# 2_Sensors.net
KiCad netlist of a schematic drawn in Altium Designer
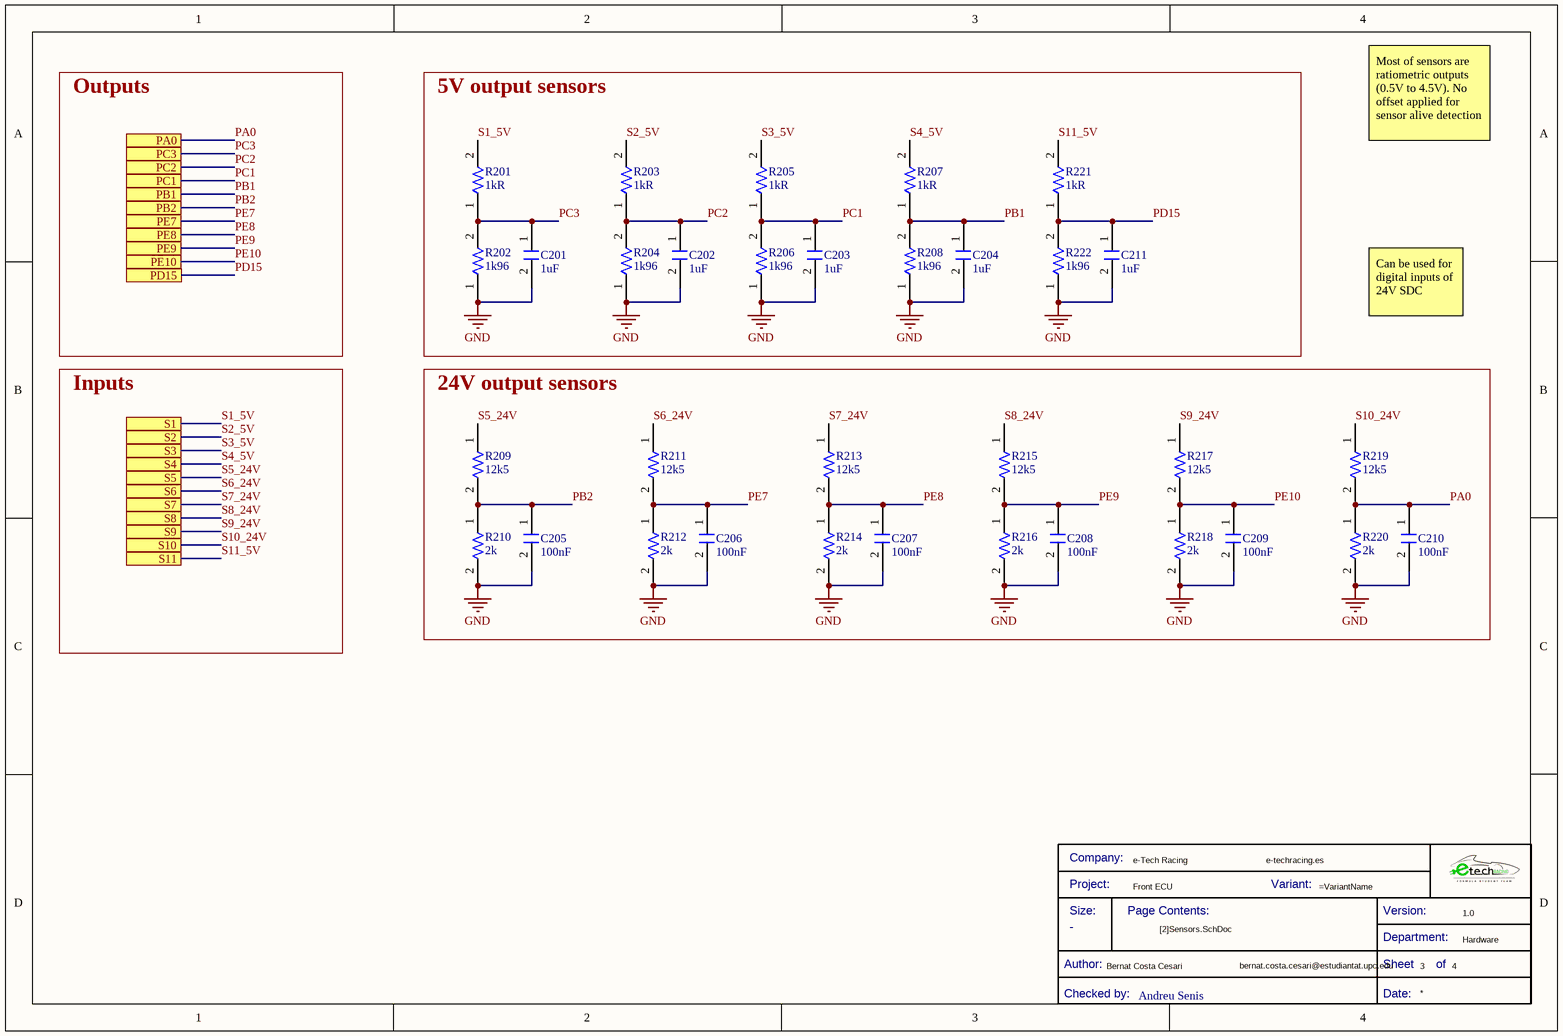
[diagram p0: [2]Sensors.SchDoc]

(export (version "E")
  (design (tool "Eeschema 10.0.6"))
  (components
    (comp (ref "C201")
      (value "885012207103")
      (footprint "C0805FNPC-R")
      (fields
        (field (name "TOLERANCE") "10%")
        (field (name "CAPACITANCE") "1uF")
        (field (name ".CREATOR") "GP")
      )
      (libsource (lib "Passives") (part "C1u-50V-0805FNPC-X7R"))
    )
    (comp (ref "C202")
      (value "885012207103")
      (footprint "C0805FNPC-R")
      (fields
        (field (name "TOLERANCE") "10%")
        (field (name "CAPACITANCE") "1uF")
        (field (name ".CREATOR") "GP")
      )
      (libsource (lib "Passives") (part "C1u-50V-0805FNPC-X7R"))
    )
    (comp (ref "C203")
      (value "885012207103")
      (footprint "C0805FNPC-R")
      (fields
        (field (name "TOLERANCE") "10%")
        (field (name "CAPACITANCE") "1uF")
        (field (name ".CREATOR") "GP")
      )
      (libsource (lib "Passives") (part "C1u-50V-0805FNPC-X7R"))
    )
    (comp (ref "C204")
      (value "885012207103")
      (footprint "C0805FNPC-R")
      (fields
        (field (name "TOLERANCE") "10%")
        (field (name "CAPACITANCE") "1uF")
        (field (name ".CREATOR") "GP")
      )
      (libsource (lib "Passives") (part "C1u-50V-0805FNPC-X7R"))
    )
    (comp (ref "C205")
      (value "885012207098")
      (footprint "C0805FNPC-R")
      (description "Cap, 0.1ΜF, 50V, 10%, X7R, 0805")
      (fields
        (field (name "TOLERANCE") "10%")
        (field (name "CAPACITANCE") "100nF")
        (field (name ".CREATOR") "DR")
      )
      (libsource (lib "Passives") (part "C100n-50V-0805FNPC-X7R"))
    )
    (comp (ref "C206")
      (value "885012207098")
      (footprint "C0805FNPC-R")
      (description "Cap, 0.1ΜF, 50V, 10%, X7R, 0805")
      (fields
        (field (name "TOLERANCE") "10%")
        (field (name "CAPACITANCE") "100nF")
        (field (name ".CREATOR") "DR")
      )
      (libsource (lib "Passives") (part "C100n-50V-0805FNPC-X7R"))
    )
    (comp (ref "C207")
      (value "885012207098")
      (footprint "C0805FNPC-R")
      (description "Cap, 0.1ΜF, 50V, 10%, X7R, 0805")
      (fields
        (field (name "TOLERANCE") "10%")
        (field (name "CAPACITANCE") "100nF")
        (field (name ".CREATOR") "DR")
      )
      (libsource (lib "Passives") (part "C100n-50V-0805FNPC-X7R"))
    )
    (comp (ref "C208")
      (value "885012207098")
      (footprint "C0805FNPC-R")
      (description "Cap, 0.1ΜF, 50V, 10%, X7R, 0805")
      (fields
        (field (name "TOLERANCE") "10%")
        (field (name "CAPACITANCE") "100nF")
        (field (name ".CREATOR") "DR")
      )
      (libsource (lib "Passives") (part "C100n-50V-0805FNPC-X7R"))
    )
    (comp (ref "C209")
      (value "885012207098")
      (footprint "C0805FNPC-R")
      (description "Cap, 0.1ΜF, 50V, 10%, X7R, 0805")
      (fields
        (field (name "TOLERANCE") "10%")
        (field (name "CAPACITANCE") "100nF")
        (field (name ".CREATOR") "DR")
      )
      (libsource (lib "Passives") (part "C100n-50V-0805FNPC-X7R"))
    )
    (comp (ref "C210")
      (value "885012207098")
      (footprint "C0805FNPC-R")
      (description "Cap, 0.1ΜF, 50V, 10%, X7R, 0805")
      (fields
        (field (name "TOLERANCE") "10%")
        (field (name "CAPACITANCE") "100nF")
        (field (name ".CREATOR") "DR")
      )
      (libsource (lib "Passives") (part "C100n-50V-0805FNPC-X7R"))
    )
    (comp (ref "C211")
      (value "885012207103")
      (footprint "C0805FNPC-R")
      (fields
        (field (name "TOLERANCE") "10%")
        (field (name "CAPACITANCE") "1uF")
        (field (name ".CREATOR") "GP")
      )
      (libsource (lib "Passives") (part "C1u-50V-0805FNPC-X7R"))
    )
    (comp (ref "R201")
      (value "CR0805-JW-102ELF")
      (footprint "R0805FTK")
      (description "Res Thick Film 0805 1K Ohm 5% 1/8W ±200ppm/°C Molded SMD SMD Paper Tape on Plastic Reel")
      (fields
        (field (name "TOLERANCE") "5%")
        (field (name "RESISTANCE") "1kR")
        (field (name ".CREATOR") "GP")
      )
      (libsource (lib "Passives") (part "R1k-0805FTK"))
    )
    (comp (ref "R202")
      (value "1k96")
      (footprint "R0805FTK")
      (libsource (lib "Passives") (part "R1k96-0805FTK"))
    )
    (comp (ref "R203")
      (value "CR0805-JW-102ELF")
      (footprint "R0805FTK")
      (description "Res Thick Film 0805 1K Ohm 5% 1/8W ±200ppm/°C Molded SMD SMD Paper Tape on Plastic Reel")
      (fields
        (field (name "TOLERANCE") "5%")
        (field (name "RESISTANCE") "1kR")
        (field (name ".CREATOR") "GP")
      )
      (libsource (lib "Passives") (part "R1k-0805FTK"))
    )
    (comp (ref "R204")
      (value "1k96")
      (footprint "R0805FTK")
      (libsource (lib "Passives") (part "R1k96-0805FTK"))
    )
    (comp (ref "R205")
      (value "CR0805-JW-102ELF")
      (footprint "R0805FTK")
      (description "Res Thick Film 0805 1K Ohm 5% 1/8W ±200ppm/°C Molded SMD SMD Paper Tape on Plastic Reel")
      (fields
        (field (name "TOLERANCE") "5%")
        (field (name "RESISTANCE") "1kR")
        (field (name ".CREATOR") "GP")
      )
      (libsource (lib "Passives") (part "R1k-0805FTK"))
    )
    (comp (ref "R206")
      (value "1k96")
      (footprint "R0805FTK")
      (libsource (lib "Passives") (part "R1k96-0805FTK"))
    )
    (comp (ref "R207")
      (value "CR0805-JW-102ELF")
      (footprint "R0805FTK")
      (description "Res Thick Film 0805 1K Ohm 5% 1/8W ±200ppm/°C Molded SMD SMD Paper Tape on Plastic Reel")
      (fields
        (field (name "TOLERANCE") "5%")
        (field (name "RESISTANCE") "1kR")
        (field (name ".CREATOR") "GP")
      )
      (libsource (lib "Passives") (part "R1k-0805FTK"))
    )
    (comp (ref "R208")
      (value "1k96")
      (footprint "R0805FTK")
      (libsource (lib "Passives") (part "R1k96-0805FTK"))
    )
    (comp (ref "R209")
      (value "12k5")
      (footprint "R0805FTK")
      (libsource (lib "Passives") (part "R12k5-0805FTK"))
    )
    (comp (ref "R210") (value "2k") (footprint "R0805FTK") (libsource (lib "Passives") (part "R2k-0805FTK")))
    (comp (ref "R211")
      (value "12k5")
      (footprint "R0805FTK")
      (libsource (lib "Passives") (part "R12k5-0805FTK"))
    )
    (comp (ref "R212") (value "2k") (footprint "R0805FTK") (libsource (lib "Passives") (part "R2k-0805FTK")))
    (comp (ref "R213")
      (value "12k5")
      (footprint "R0805FTK")
      (libsource (lib "Passives") (part "R12k5-0805FTK"))
    )
    (comp (ref "R214") (value "2k") (footprint "R0805FTK") (libsource (lib "Passives") (part "R2k-0805FTK")))
    (comp (ref "R215")
      (value "12k5")
      (footprint "R0805FTK")
      (libsource (lib "Passives") (part "R12k5-0805FTK"))
    )
    (comp (ref "R216") (value "2k") (footprint "R0805FTK") (libsource (lib "Passives") (part "R2k-0805FTK")))
    (comp (ref "R217")
      (value "12k5")
      (footprint "R0805FTK")
      (libsource (lib "Passives") (part "R12k5-0805FTK"))
    )
    (comp (ref "R218") (value "2k") (footprint "R0805FTK") (libsource (lib "Passives") (part "R2k-0805FTK")))
    (comp (ref "R219")
      (value "12k5")
      (footprint "R0805FTK")
      (libsource (lib "Passives") (part "R12k5-0805FTK"))
    )
    (comp (ref "R220") (value "2k") (footprint "R0805FTK") (libsource (lib "Passives") (part "R2k-0805FTK")))
    (comp (ref "R221")
      (value "CR0805-JW-102ELF")
      (footprint "R0805FTK")
      (description "Res Thick Film 0805 1K Ohm 5% 1/8W ±200ppm/°C Molded SMD SMD Paper Tape on Plastic Reel")
      (fields
        (field (name "TOLERANCE") "5%")
        (field (name "RESISTANCE") "1kR")
        (field (name ".CREATOR") "GP")
      )
      (libsource (lib "Passives") (part "R1k-0805FTK"))
    )
    (comp (ref "R222")
      (value "1k96")
      (footprint "R0805FTK")
      (libsource (lib "Passives") (part "R1k96-0805FTK"))
    )
  )
  (nets
    (net (code "1") (name "/PA0") (class "Default")
      (node (ref "C210") (pin "1") (pinfunction "1_1") (pintype "passive"))
      (node (ref "R219") (pin "2") (pinfunction "2_2") (pintype "passive"))
      (node (ref "R220") (pin "1") (pinfunction "1_1") (pintype "passive"))
    )
    (net (code "2") (name "/PB1") (class "Default")
      (node (ref "C204") (pin "1") (pinfunction "1_1") (pintype "passive"))
      (node (ref "R207") (pin "1") (pinfunction "1_1") (pintype "passive"))
      (node (ref "R208") (pin "2") (pinfunction "2_2") (pintype "passive"))
    )
    (net (code "3") (name "/PB2") (class "Default")
      (node (ref "C205") (pin "1") (pinfunction "1_1") (pintype "passive"))
      (node (ref "R209") (pin "2") (pinfunction "2_2") (pintype "passive"))
      (node (ref "R210") (pin "1") (pinfunction "1_1") (pintype "passive"))
    )
    (net (code "4") (name "/PC1") (class "Default")
      (node (ref "C203") (pin "1") (pinfunction "1_1") (pintype "passive"))
      (node (ref "R205") (pin "1") (pinfunction "1_1") (pintype "passive"))
      (node (ref "R206") (pin "2") (pinfunction "2_2") (pintype "passive"))
    )
    (net (code "5") (name "/PC2") (class "Default")
      (node (ref "C202") (pin "1") (pinfunction "1_1") (pintype "passive"))
      (node (ref "R203") (pin "1") (pinfunction "1_1") (pintype "passive"))
      (node (ref "R204") (pin "2") (pinfunction "2_2") (pintype "passive"))
    )
    (net (code "6") (name "/PC3") (class "Default")
      (node (ref "C201") (pin "1") (pinfunction "1_1") (pintype "passive"))
      (node (ref "R201") (pin "1") (pinfunction "1_1") (pintype "passive"))
      (node (ref "R202") (pin "2") (pinfunction "2_2") (pintype "passive"))
    )
    (net (code "7") (name "/PD15") (class "Default")
      (node (ref "C211") (pin "1") (pinfunction "1_1") (pintype "passive"))
      (node (ref "R221") (pin "1") (pinfunction "1_1") (pintype "passive"))
      (node (ref "R222") (pin "2") (pinfunction "2_2") (pintype "passive"))
    )
    (net (code "8") (name "/PE7") (class "Default")
      (node (ref "C206") (pin "1") (pinfunction "1_1") (pintype "passive"))
      (node (ref "R211") (pin "2") (pinfunction "2_2") (pintype "passive"))
      (node (ref "R212") (pin "1") (pinfunction "1_1") (pintype "passive"))
    )
    (net (code "9") (name "/PE8") (class "Default")
      (node (ref "C207") (pin "1") (pinfunction "1_1") (pintype "passive"))
      (node (ref "R213") (pin "2") (pinfunction "2_2") (pintype "passive"))
      (node (ref "R214") (pin "1") (pinfunction "1_1") (pintype "passive"))
    )
    (net (code "10") (name "/PE9") (class "Default")
      (node (ref "C208") (pin "1") (pinfunction "1_1") (pintype "passive"))
      (node (ref "R215") (pin "2") (pinfunction "2_2") (pintype "passive"))
      (node (ref "R216") (pin "1") (pinfunction "1_1") (pintype "passive"))
    )
    (net (code "11") (name "/PE10") (class "Default")
      (node (ref "C209") (pin "1") (pinfunction "1_1") (pintype "passive"))
      (node (ref "R217") (pin "2") (pinfunction "2_2") (pintype "passive"))
      (node (ref "R218") (pin "1") (pinfunction "1_1") (pintype "passive"))
    )
    (net (code "12") (name "/S1_5V") (class "Default")
      (node (ref "R201") (pin "2") (pinfunction "2_2") (pintype "passive"))
    )
    (net (code "13") (name "/S2_5V") (class "Default")
      (node (ref "R203") (pin "2") (pinfunction "2_2") (pintype "passive"))
    )
    (net (code "14") (name "/S3_5V") (class "Default")
      (node (ref "R205") (pin "2") (pinfunction "2_2") (pintype "passive"))
    )
    (net (code "15") (name "/S4_5V") (class "Default")
      (node (ref "R207") (pin "2") (pinfunction "2_2") (pintype "passive"))
    )
    (net (code "16") (name "/S5_24V") (class "Default")
      (node (ref "R209") (pin "1") (pinfunction "1_1") (pintype "passive"))
    )
    (net (code "17") (name "/S6_24V") (class "Default")
      (node (ref "R211") (pin "1") (pinfunction "1_1") (pintype "passive"))
    )
    (net (code "18") (name "/S7_24V") (class "Default")
      (node (ref "R213") (pin "1") (pinfunction "1_1") (pintype "passive"))
    )
    (net (code "19") (name "/S8_24V") (class "Default")
      (node (ref "R215") (pin "1") (pinfunction "1_1") (pintype "passive"))
    )
    (net (code "20") (name "/S9_24V") (class "Default")
      (node (ref "R217") (pin "1") (pinfunction "1_1") (pintype "passive"))
    )
    (net (code "21") (name "/S10_24V") (class "Default")
      (node (ref "R219") (pin "1") (pinfunction "1_1") (pintype "passive"))
    )
    (net (code "22") (name "/S11_5V") (class "Default")
      (node (ref "R221") (pin "2") (pinfunction "2_2") (pintype "passive"))
    )
    (net (code "23") (name "GND") (class "Default")
      (node (ref "C201") (pin "2") (pinfunction "2_2") (pintype "passive"))
      (node (ref "C202") (pin "2") (pinfunction "2_2") (pintype "passive"))
      (node (ref "C203") (pin "2") (pinfunction "2_2") (pintype "passive"))
      (node (ref "C204") (pin "2") (pinfunction "2_2") (pintype "passive"))
      (node (ref "C205") (pin "2") (pinfunction "2_2") (pintype "passive"))
      (node (ref "C206") (pin "2") (pinfunction "2_2") (pintype "passive"))
      (node (ref "C207") (pin "2") (pinfunction "2_2") (pintype "passive"))
      (node (ref "C208") (pin "2") (pinfunction "2_2") (pintype "passive"))
      (node (ref "C209") (pin "2") (pinfunction "2_2") (pintype "passive"))
      (node (ref "C210") (pin "2") (pinfunction "2_2") (pintype "passive"))
      (node (ref "C211") (pin "2") (pinfunction "2_2") (pintype "passive"))
      (node (ref "R202") (pin "1") (pinfunction "1_1") (pintype "passive"))
      (node (ref "R204") (pin "1") (pinfunction "1_1") (pintype "passive"))
      (node (ref "R206") (pin "1") (pinfunction "1_1") (pintype "passive"))
      (node (ref "R208") (pin "1") (pinfunction "1_1") (pintype "passive"))
      (node (ref "R210") (pin "2") (pinfunction "2_2") (pintype "passive"))
      (node (ref "R212") (pin "2") (pinfunction "2_2") (pintype "passive"))
      (node (ref "R214") (pin "2") (pinfunction "2_2") (pintype "passive"))
      (node (ref "R216") (pin "2") (pinfunction "2_2") (pintype "passive"))
      (node (ref "R218") (pin "2") (pinfunction "2_2") (pintype "passive"))
      (node (ref "R220") (pin "2") (pinfunction "2_2") (pintype "passive"))
      (node (ref "R222") (pin "1") (pinfunction "1_1") (pintype "passive"))
    )
  )
)
